# LPS28DFW.net
KiCad netlist of a schematic drawn in EAGLE
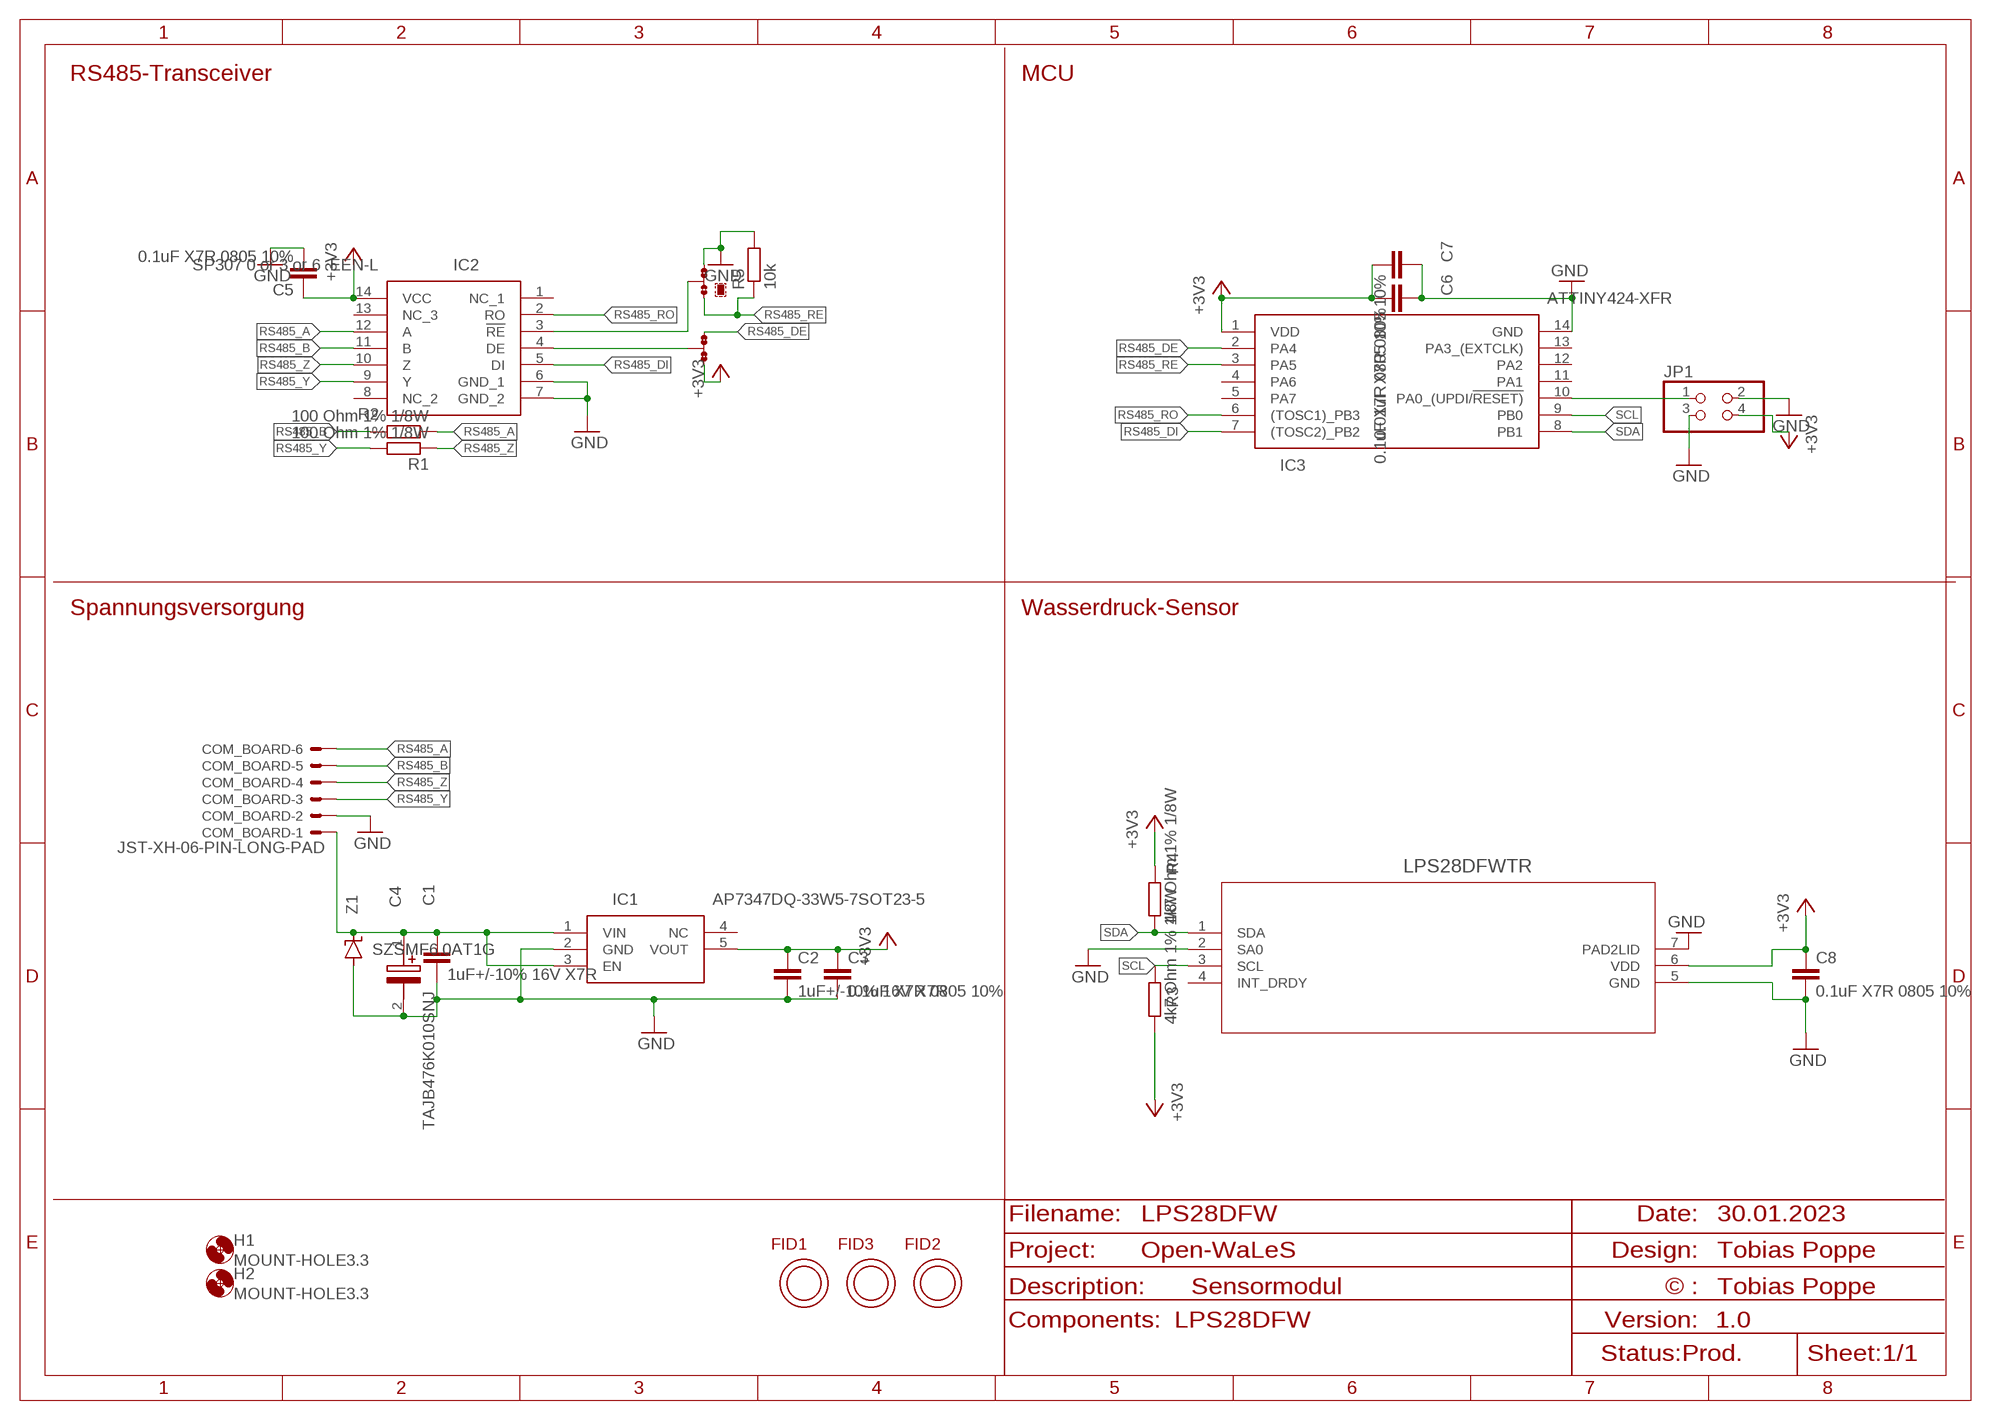
[diagram p0: schematic, sheet 1]

(export (version "E")
  (design (tool "Eeschema 10.0.6"))
  (components
    (comp (ref "C1")
      (value "1uF+/-10% 16V X7R")
      (footprint "eagle-import:C0805")
      (libsource (lib "eagle-import") (part "C-EUC0805"))
    )
    (comp (ref "C2")
      (value "1uF+/-10% 16V X7R")
      (footprint "eagle-import:C0805")
      (libsource (lib "eagle-import") (part "C-EUC0805"))
    )
    (comp (ref "C3")
      (value "0.1uF X7R 0805 10%")
      (footprint "eagle-import:C0805")
      (libsource (lib "eagle-import") (part "C-EUC0805"))
    )
    (comp (ref "C4")
      (value "TAJB476K010SNJ")
      (footprint "eagle-import:CAPPM3528X210N")
      (fields (field (name "MOUSER_PART_NUMBER") "581-TAJB476K010SNJ"))
      (libsource (lib "eagle-import") (part "TAJB476K010SNJ"))
    )
    (comp (ref "C5")
      (value "0.1uF X7R 0805 10%")
      (footprint "eagle-import:C0805")
      (libsource (lib "eagle-import") (part "C-EUC0805"))
    )
    (comp (ref "C6")
      (value "0.1uF X7R 0805 10%")
      (footprint "eagle-import:C0805")
      (libsource (lib "eagle-import") (part "C-EUC0805"))
    )
    (comp (ref "C7")
      (value "0.01uF X7R 0805 10%")
      (footprint "eagle-import:C0805")
      (libsource (lib "eagle-import") (part "C-EUC0805"))
    )
    (comp (ref "C8")
      (value "0.1uF X7R 0805 10%")
      (footprint "eagle-import:C0805")
      (libsource (lib "eagle-import") (part "C-EUC0805"))
    )
    (comp (ref "C11")
      (value "LPS28DFWTR")
      (footprint "eagle-import:CCLGA7_LPS28DFWTR_STM")
      (fields (field (name "COPYRIGHT") "Copyright (C) 2022 Ultra Librarian. All rights reserved."))
      (libsource (lib "eagle-import") (part "LPS28DFWTR"))
    )
    (comp (ref "COM_BOARD")
      (value "JST-XH-06-PIN-LONG-PAD")
      (footprint "eagle-import:JST-XH-06-PACKAGE-LONG-PAD")
      (libsource (lib "eagle-import") (part "JST-XH-06-PIN-LONG-PAD"))
    )
    (comp (ref "FID1")
      (value "OPEN-PNP-FIDUCIAL")
      (footprint "eagle-import:OPEN-PNP-FIDUCIAL")
      (libsource (lib "eagle-import") (part "OPEN-PNP-FIDUCIAL"))
    )
    (comp (ref "FID2")
      (value "OPEN-PNP-FIDUCIAL")
      (footprint "eagle-import:OPEN-PNP-FIDUCIAL")
      (libsource (lib "eagle-import") (part "OPEN-PNP-FIDUCIAL"))
    )
    (comp (ref "FID3")
      (value "OPEN-PNP-FIDUCIAL")
      (footprint "eagle-import:OPEN-PNP-FIDUCIAL")
      (libsource (lib "eagle-import") (part "OPEN-PNP-FIDUCIAL"))
    )
    (comp (ref "H1")
      (value "MOUNT-HOLE3.3")
      (footprint "eagle-import:3,3")
      (libsource (lib "eagle-import") (part "MOUNT-HOLE3.3"))
    )
    (comp (ref "H2")
      (value "MOUNT-HOLE3.3")
      (footprint "eagle-import:3,3")
      (libsource (lib "eagle-import") (part "MOUNT-HOLE3.3"))
    )
    (comp (ref "IC1")
      (value "AP7347DQ-33W5-7SOT23-5")
      (footprint "eagle-import:SOT95P240X110-5N")
      (libsource (lib "eagle-import") (part "AP7347DQ-33W5-7SOT23-5"))
    )
    (comp (ref "IC2")
      (value "SP307 0 or 3 or 6 EEN-L")
      (footprint "eagle-import:SOIC127P600X175-14N")
      (fields
        (field (name "MANUFACTURER_PART_NUMBER") "SP3076EEN-L")
        (field (name "MOUSER_PART_NUMBER") "701-SP3076EEN-L")
      )
      (libsource (lib "eagle-import") (part "SP3076EEN-L"))
    )
    (comp (ref "IC3")
      (value "ATTINY424-XFR")
      (footprint "eagle-import:SOP65P640X120-14N")
      (fields (field (name "MOUSER_PART_NUMBER") "579-ATTINY424-XFR"))
      (libsource (lib "eagle-import") (part "ATTINY424-XFR"))
    )
    (comp (ref "JMP1")
      (value "0R-JUMPA")
      (footprint "eagle-import:A0R-JMP")
      (libsource (lib "eagle-import") (part "0R-JUMPA"))
    )
    (comp (ref "JMP2")
      (value "0R-JUMPA")
      (footprint "eagle-import:A0R-JMP")
      (libsource (lib "eagle-import") (part "0R-JUMPA"))
    )
    (comp (ref "JP1")
      (value "PINHD-2X2")
      (footprint "eagle-import:2X02")
      (libsource (lib "eagle-import") (part "PINHD-2X2"))
    )
    (comp (ref "R1")
      (value "100 Ohm 1% 1/8W")
      (footprint "eagle-import:R0805")
      (libsource (lib "eagle-import") (part "R-EU_R0805"))
    )
    (comp (ref "R2")
      (value "100 Ohm 1% 1/8W")
      (footprint "eagle-import:R0805")
      (libsource (lib "eagle-import") (part "R-EU_R0805"))
    )
    (comp (ref "R3")
      (value "4k7 Ohm 1% 1/8W")
      (footprint "eagle-import:R0805")
      (libsource (lib "eagle-import") (part "R-EU_R0805"))
    )
    (comp (ref "R4")
      (value "4k7 Ohm 1% 1/8W")
      (footprint "eagle-import:R0805")
      (libsource (lib "eagle-import") (part "R-EU_R0805"))
    )
    (comp (ref "R5")
      (value "10k")
      (footprint "eagle-import:M0805")
      (libsource (lib "eagle-import") (part "R-EU_M0805"))
    )
    (comp (ref "Z1")
      (value "SZSMF6.0AT1G")
      (footprint "eagle-import:SOD123")
      (libsource (lib "eagle-import") (part "SZSMF_XX"))
    )
  )
  (nets
    (net (code "1") (name "+3V3") (class "Default")
      (node (ref "C11") (pin "6") (pinfunction "VDD_6") (pintype "power_in"))
      (node (ref "C2") (pin "1") (pinfunction "1_1") (pintype "passive"))
      (node (ref "C3") (pin "1") (pinfunction "1_1") (pintype "passive"))
      (node (ref "C5") (pin "1") (pinfunction "1_1") (pintype "passive"))
      (node (ref "C6") (pin "2") (pinfunction "2_2") (pintype "passive"))
      (node (ref "C7") (pin "2") (pinfunction "2_2") (pintype "passive"))
      (node (ref "C8") (pin "1") (pinfunction "1_1") (pintype "passive"))
      (node (ref "IC1") (pin "5") (pinfunction "VOUT_5") (pintype "bidirectional"))
      (node (ref "IC2") (pin "14") (pinfunction "VCC_14") (pintype "bidirectional"))
      (node (ref "IC3") (pin "1") (pinfunction "VDD_1") (pintype "bidirectional"))
      (node (ref "JMP1") (pin "1") (pinfunction "1_1") (pintype "passive"))
      (node (ref "JP1") (pin "4") (pinfunction "4_4") (pintype "passive"))
      (node (ref "R3") (pin "1") (pinfunction "1_1") (pintype "passive"))
      (node (ref "R4") (pin "2") (pinfunction "2_2") (pintype "passive"))
    )
    (net (code "2") (name "GND") (class "Default")
      (node (ref "C1") (pin "2") (pinfunction "2_2") (pintype "passive"))
      (node (ref "C11") (pin "2") (pinfunction "SA0_2") (pintype "bidirectional"))
      (node (ref "C11") (pin "5") (pinfunction "GND_5") (pintype "passive"))
      (node (ref "C11") (pin "7") (pinfunction "PAD2LID_7") (pintype "bidirectional"))
      (node (ref "C2") (pin "2") (pinfunction "2_2") (pintype "passive"))
      (node (ref "C3") (pin "2") (pinfunction "2_2") (pintype "passive"))
      (node (ref "C4") (pin "2") (pinfunction "-_2") (pintype "bidirectional"))
      (node (ref "C5") (pin "2") (pinfunction "2_2") (pintype "passive"))
      (node (ref "C6") (pin "1") (pinfunction "1_1") (pintype "passive"))
      (node (ref "C7") (pin "1") (pinfunction "1_1") (pintype "passive"))
      (node (ref "C8") (pin "2") (pinfunction "2_2") (pintype "passive"))
      (node (ref "COM_BOARD") (pin "2") (pinfunction "S_2") (pintype "passive"))
      (node (ref "IC1") (pin "2") (pinfunction "GND_2") (pintype "bidirectional"))
      (node (ref "IC2") (pin "6") (pinfunction "GND_1_6") (pintype "bidirectional"))
      (node (ref "IC2") (pin "7") (pinfunction "GND_2_7") (pintype "bidirectional"))
      (node (ref "IC3") (pin "14") (pinfunction "GND_14") (pintype "bidirectional"))
      (node (ref "JMP2") (pin "3") (pinfunction "3_3") (pintype "passive"))
      (node (ref "JP1") (pin "2") (pinfunction "2_2") (pintype "passive"))
      (node (ref "JP1") (pin "3") (pinfunction "3_3") (pintype "passive"))
      (node (ref "R5") (pin "2") (pinfunction "2_2") (pintype "passive"))
      (node (ref "Z1") (pin "A") (pinfunction "A_A") (pintype "passive"))
    )
    (net (code "3") (name "Net-(C4-+)") (class "Default")
      (node (ref "C1") (pin "1") (pinfunction "1_1") (pintype "passive"))
      (node (ref "C4") (pin "1") (pinfunction "+_1") (pintype "bidirectional"))
      (node (ref "COM_BOARD") (pin "1") (pinfunction "S_1") (pintype "passive"))
      (node (ref "IC1") (pin "1") (pinfunction "VIN_1") (pintype "bidirectional"))
      (node (ref "IC1") (pin "3") (pinfunction "EN_3") (pintype "bidirectional"))
      (node (ref "Z1") (pin "C") (pinfunction "C_C") (pintype "passive"))
    )
    (net (code "4") (name "Net-(IC2-DE)") (class "Default")
      (node (ref "IC2") (pin "4") (pinfunction "DE_4") (pintype "bidirectional"))
      (node (ref "JMP1") (pin "2") (pinfunction "2_2") (pintype "passive"))
    )
    (net (code "5") (name "Net-(IC2-~{RE})") (class "Default")
      (node (ref "IC2") (pin "3") (pinfunction "~{RE}_3") (pintype "bidirectional"))
      (node (ref "JMP2") (pin "2") (pinfunction "2_2") (pintype "passive"))
    )
    (net (code "6") (name "Net-(IC3-PA0_(UPDI{slash}~{RESET}))") (class "Default")
      (node (ref "IC3") (pin "10") (pinfunction "PA0_(UPDI/~{RESET})_10") (pintype "bidirectional"))
      (node (ref "JP1") (pin "1") (pinfunction "1_1") (pintype "passive"))
    )
    (net (code "7") (name "RS485_A") (class "Default")
      (node (ref "COM_BOARD") (pin "6") (pinfunction "S_6") (pintype "passive"))
      (node (ref "IC2") (pin "12") (pinfunction "A_12") (pintype "bidirectional"))
      (node (ref "R2") (pin "1") (pinfunction "1_1") (pintype "passive"))
    )
    (net (code "8") (name "RS485_B") (class "Default")
      (node (ref "COM_BOARD") (pin "5") (pinfunction "S_5") (pintype "passive"))
      (node (ref "IC2") (pin "11") (pinfunction "B_11") (pintype "bidirectional"))
      (node (ref "R2") (pin "2") (pinfunction "2_2") (pintype "passive"))
    )
    (net (code "9") (name "RS485_DE") (class "Default")
      (node (ref "IC3") (pin "2") (pinfunction "PA4_2") (pintype "bidirectional"))
      (node (ref "JMP1") (pin "3") (pinfunction "3_3") (pintype "passive"))
    )
    (net (code "10") (name "RS485_DI") (class "Default")
      (node (ref "IC2") (pin "5") (pinfunction "DI_5") (pintype "bidirectional"))
      (node (ref "IC3") (pin "7") (pinfunction "(TOSC2)_PB2_7") (pintype "bidirectional"))
    )
    (net (code "11") (name "RS485_RE") (class "Default")
      (node (ref "IC3") (pin "3") (pinfunction "PA5_3") (pintype "bidirectional"))
      (node (ref "JMP2") (pin "1") (pinfunction "1_1") (pintype "passive"))
      (node (ref "R5") (pin "1") (pinfunction "1_1") (pintype "passive"))
    )
    (net (code "12") (name "RS485_RO") (class "Default")
      (node (ref "IC2") (pin "2") (pinfunction "RO_2") (pintype "bidirectional"))
      (node (ref "IC3") (pin "6") (pinfunction "(TOSC1)_PB3_6") (pintype "bidirectional"))
    )
    (net (code "13") (name "RS485_Y") (class "Default")
      (node (ref "COM_BOARD") (pin "3") (pinfunction "S_3") (pintype "passive"))
      (node (ref "IC2") (pin "9") (pinfunction "Y_9") (pintype "bidirectional"))
      (node (ref "R1") (pin "2") (pinfunction "2_2") (pintype "passive"))
    )
    (net (code "14") (name "RS485_Z") (class "Default")
      (node (ref "COM_BOARD") (pin "4") (pinfunction "S_4") (pintype "passive"))
      (node (ref "IC2") (pin "10") (pinfunction "Z_10") (pintype "bidirectional"))
      (node (ref "R1") (pin "1") (pinfunction "1_1") (pintype "passive"))
    )
    (net (code "15") (name "SCL") (class "Default")
      (node (ref "C11") (pin "3") (pinfunction "SCL_3") (pintype "bidirectional"))
      (node (ref "IC3") (pin "9") (pinfunction "PB0_9") (pintype "bidirectional"))
      (node (ref "R3") (pin "2") (pinfunction "2_2") (pintype "passive"))
    )
    (net (code "16") (name "SDA") (class "Default")
      (node (ref "C11") (pin "1") (pinfunction "SDA_1") (pintype "bidirectional"))
      (node (ref "IC3") (pin "8") (pinfunction "PB1_8") (pintype "bidirectional"))
      (node (ref "R4") (pin "1") (pinfunction "1_1") (pintype "passive"))
    )
    (net (code "17") (name "unconnected-(C11-INT_DRDY-Pad4)") (class "Default")
      (node (ref "C11") (pin "4") (pinfunction "INT_DRDY_4") (pintype "input"))
    )
    (net (code "18") (name "unconnected-(IC1-NC-Pad4)") (class "Default")
      (node (ref "IC1") (pin "4") (pinfunction "NC_4") (pintype "no_connect"))
    )
    (net (code "19") (name "unconnected-(IC2-NC_1-Pad1)") (class "Default")
      (node (ref "IC2") (pin "1") (pinfunction "NC_1_1") (pintype "bidirectional"))
    )
    (net (code "20") (name "unconnected-(IC2-NC_2-Pad8)") (class "Default")
      (node (ref "IC2") (pin "8") (pinfunction "NC_2_8") (pintype "bidirectional"))
    )
    (net (code "21") (name "unconnected-(IC2-NC_3-Pad13)") (class "Default")
      (node (ref "IC2") (pin "13") (pinfunction "NC_3_13") (pintype "bidirectional"))
    )
    (net (code "22") (name "unconnected-(IC3-PA1-Pad11)") (class "Default")
      (node (ref "IC3") (pin "11") (pinfunction "PA1_11") (pintype "bidirectional"))
    )
    (net (code "23") (name "unconnected-(IC3-PA2-Pad12)") (class "Default")
      (node (ref "IC3") (pin "12") (pinfunction "PA2_12") (pintype "bidirectional"))
    )
    (net (code "24") (name "unconnected-(IC3-PA3_(EXTCLK)-Pad13)") (class "Default")
      (node (ref "IC3") (pin "13") (pinfunction "PA3_(EXTCLK)_13") (pintype "bidirectional"))
    )
    (net (code "25") (name "unconnected-(IC3-PA6-Pad4)") (class "Default")
      (node (ref "IC3") (pin "4") (pinfunction "PA6_4") (pintype "bidirectional"))
    )
    (net (code "26") (name "unconnected-(IC3-PA7-Pad5)") (class "Default")
      (node (ref "IC3") (pin "5") (pinfunction "PA7_5") (pintype "bidirectional"))
    )
  )
)
